# PCB_LCEDA.net
KiCad netlist of a schematic drawn in EasyEDA
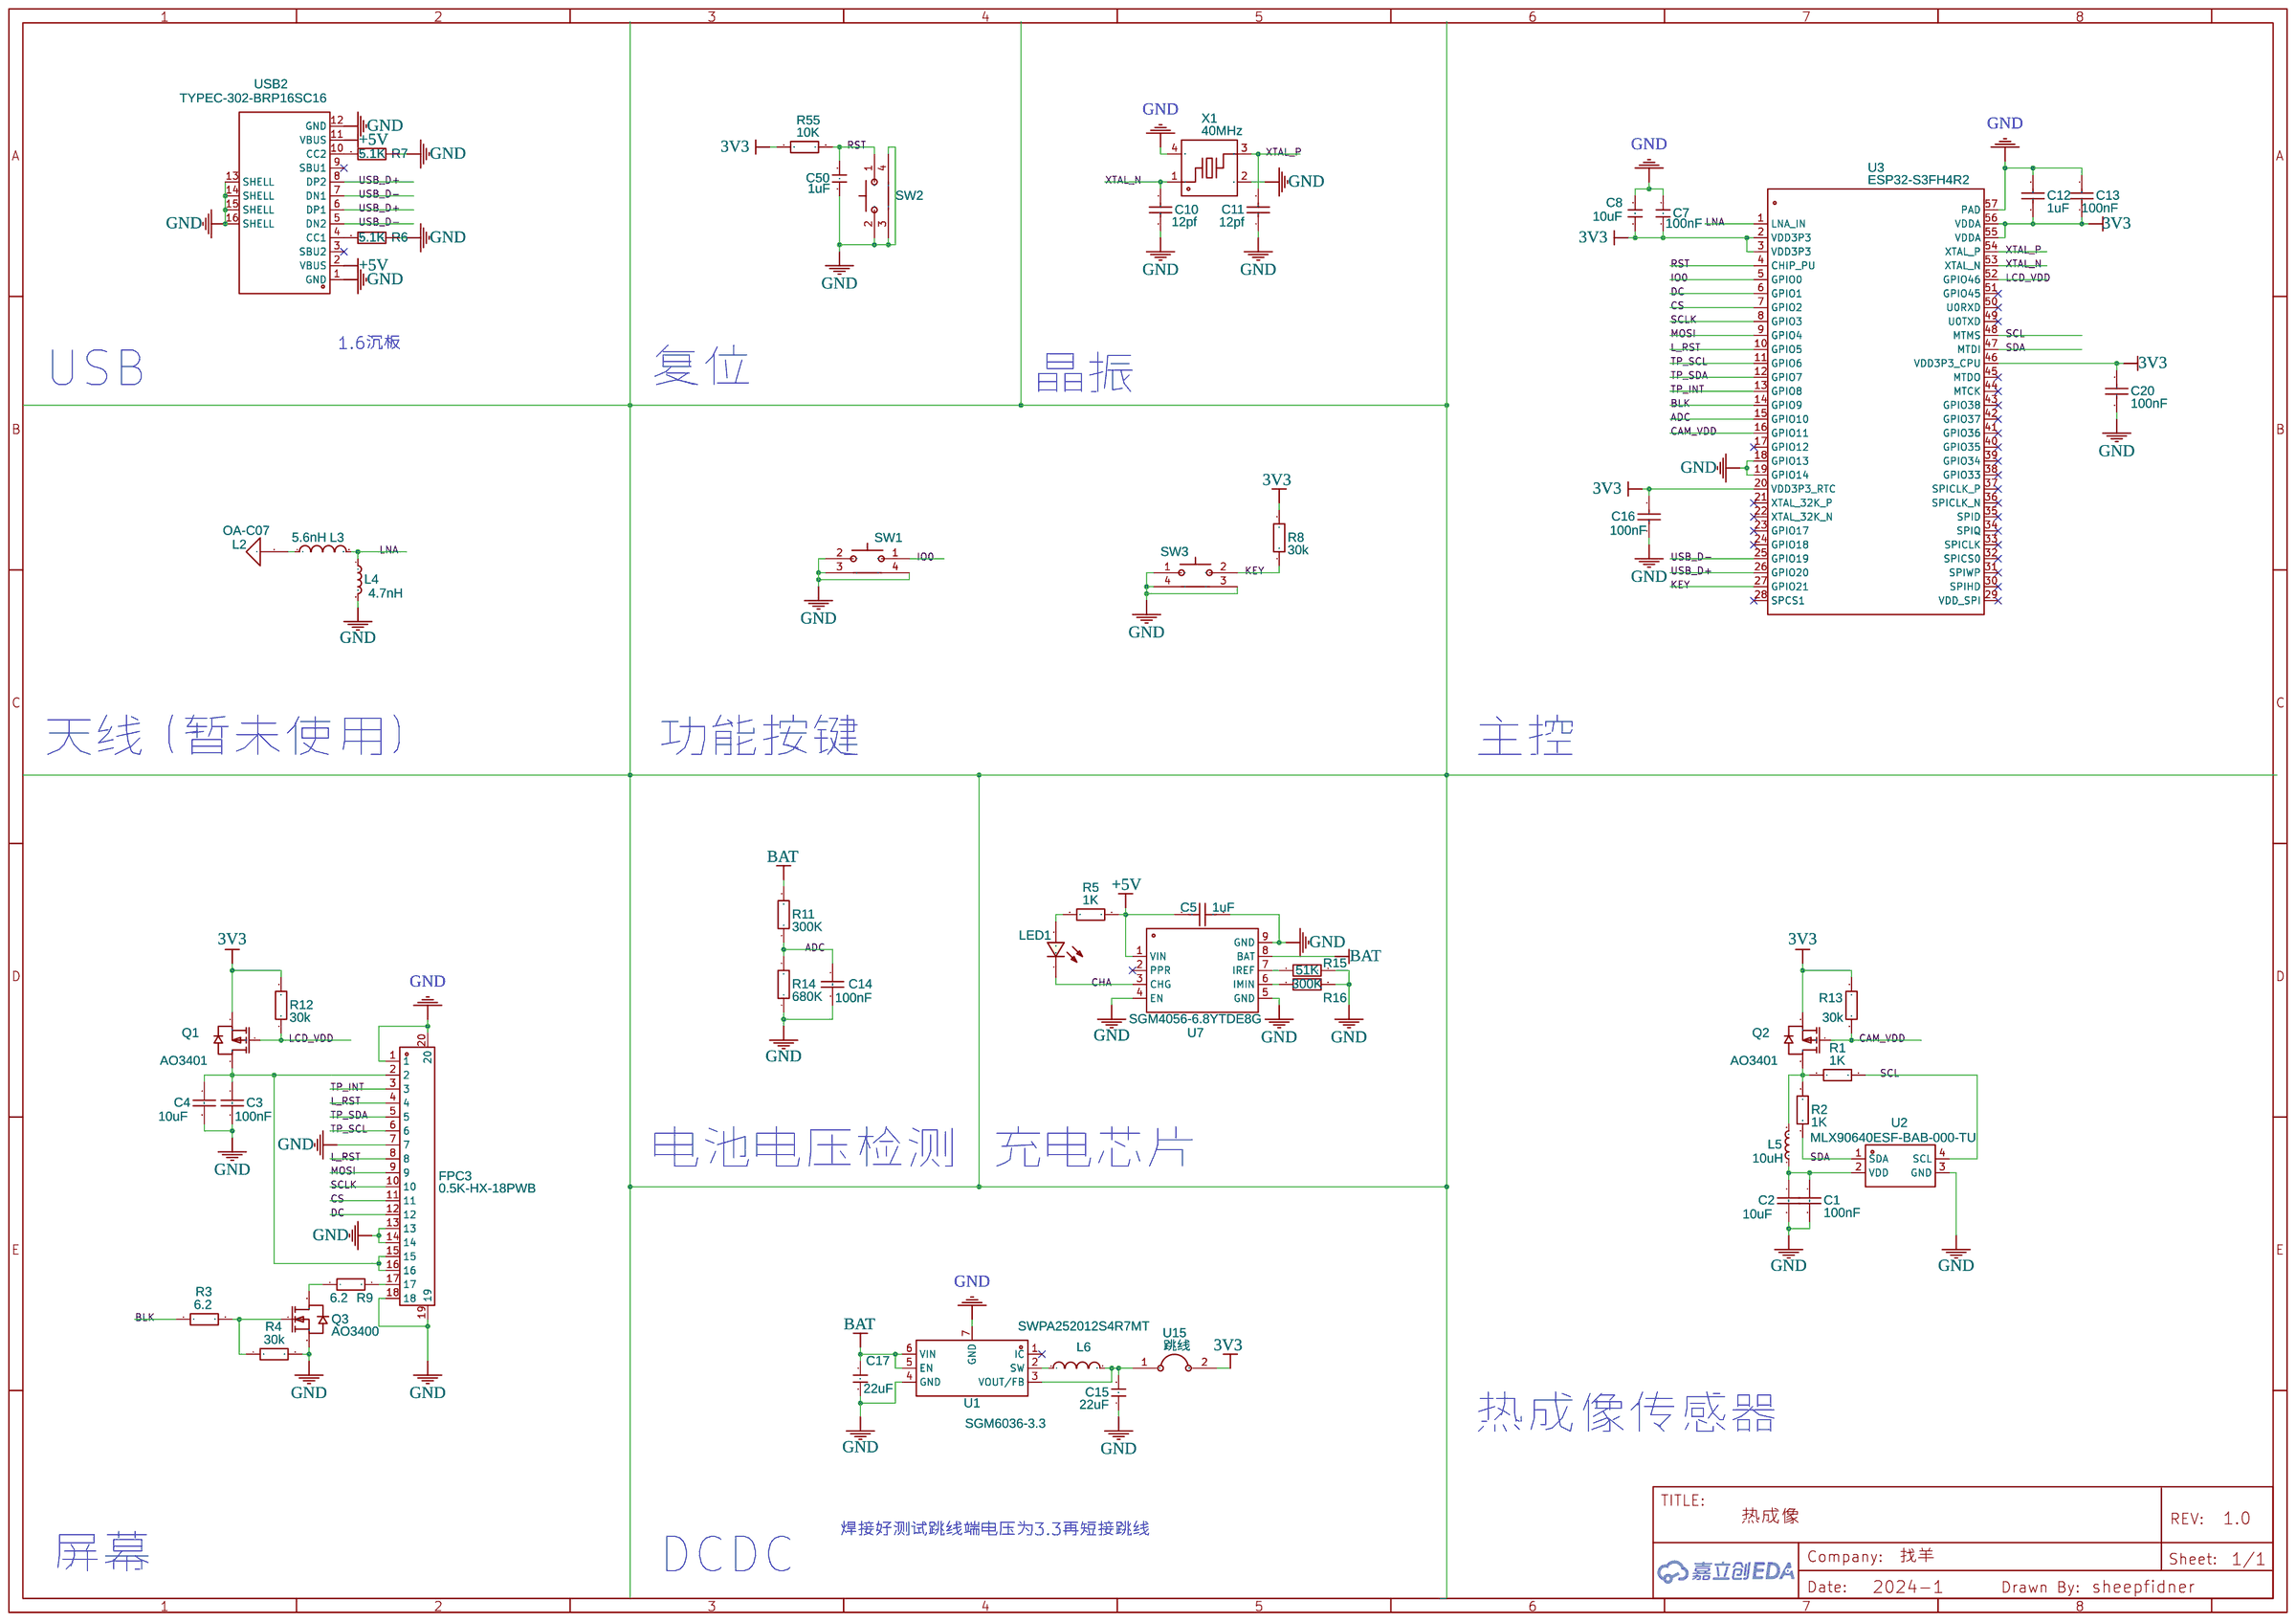
[diagram p0: schematic sheet]

(export (version "E")
  (design (tool "Eeschema 10.0.6"))
  (components
    (comp (ref "C1") (value "100nF") (libsource (lib "") (part "cap 0603_3")))
    (comp (ref "C2") (value "10uF") (libsource (lib "") (part "cap 0603")))
    (comp (ref "C3") (value "100nF") (libsource (lib "") (part "cap 0603")))
    (comp (ref "C4") (value "10uF") (libsource (lib "") (part "cap 0603")))
    (comp (ref "C5") (value "1uF") (libsource (lib "") (part "cap 0603_4")))
    (comp (ref "C7") (value "100nF") (libsource (lib "") (part "cap 0603_1")))
    (comp (ref "C8") (value "10uF") (libsource (lib "") (part "cap 0603_2")))
    (comp (ref "C10") (value "12pf") (libsource (lib "") (part "cap 0402")))
    (comp (ref "C11") (value "12pf") (libsource (lib "") (part "cap 0402_1")))
    (comp (ref "C12") (value "1uF") (libsource (lib "") (part "cap 0402_2")))
    (comp (ref "C13") (value "100nF") (libsource (lib "") (part "cap 0402_2")))
    (comp (ref "C14") (value "100nF") (libsource (lib "") (part "cap 0603")))
    (comp (ref "C15") (value "22uF") (libsource (lib "") (part "cap 0603_2")))
    (comp (ref "C16") (value "100nF") (libsource (lib "") (part "cap 0402")))
    (comp (ref "C17") (value "22uF") (libsource (lib "") (part "cap 0603_1")))
    (comp (ref "C20") (value "100nF") (libsource (lib "") (part "cap 0402")))
    (comp (ref "C50") (value "1uF") (libsource (lib "") (part "cap 0603_1")))
    (comp (ref "FPC3") (value "0.5K-HX-18PWB") (libsource (lib "") (part "0.5K-HX-18PWB")))
    (comp (ref "L2") (value "OA-C07") (libsource (lib "") (part "OA-C07")))
    (comp (ref "L3") (value "5.6nH") (libsource (lib "") (part "L-0402")))
    (comp (ref "L4") (value "4.7nH") (libsource (lib "") (part "L 0603")))
    (comp (ref "L5") (value "10uH") (libsource (lib "") (part "0805-L")))
    (comp (ref "L6") (value "SWPA252012S4R7MT") (libsource (lib "") (part "SWPA252012S2R2N")))
    (comp (ref "LED1") (value "led-0603") (libsource (lib "") (part "led-0603")))
    (comp (ref "Q1")
      (value "AO3401")
      (fields (field (name "Manufacturer") "IDCHIP(英锐芯)"))
      (libsource (lib "") (part "AO3401_C2848197"))
    )
    (comp (ref "Q2")
      (value "AO3401")
      (fields (field (name "Manufacturer") "IDCHIP(英锐芯)"))
      (libsource (lib "") (part "AO3401_C2848197"))
    )
    (comp (ref "Q3")
      (value "AO3400")
      (fields (field (name "Manufacturer") "IDCHIP(英锐芯)"))
      (libsource (lib "") (part "AO3400_C2848198"))
    )
    (comp (ref "R1") (value "1K") (libsource (lib "") (part "res-0603_1")))
    (comp (ref "R2") (value "1K") (libsource (lib "") (part "res-0603_2")))
    (comp (ref "R3") (value "6.2") (libsource (lib "") (part "res-0603")))
    (comp (ref "R4") (value "30k") (libsource (lib "") (part "res-0603")))
    (comp (ref "R5") (value "1K") (libsource (lib "") (part "res-0603_1")))
    (comp (ref "R6") (value "5.1K") (libsource (lib "") (part "res-0603")))
    (comp (ref "R7") (value "5.1K") (libsource (lib "") (part "res-0603_1")))
    (comp (ref "R8") (value "30k") (libsource (lib "") (part "res-0603_2")))
    (comp (ref "R9") (value "6.2") (libsource (lib "") (part "res-0603")))
    (comp (ref "R11") (value "300K") (libsource (lib "") (part "res-0603_2")))
    (comp (ref "R12") (value "30k") (libsource (lib "") (part "res-0603_2")))
    (comp (ref "R13") (value "30k") (libsource (lib "") (part "res-0603_2")))
    (comp (ref "R14") (value "680K") (libsource (lib "") (part "res-0603_2")))
    (comp (ref "R15") (value "51K") (libsource (lib "") (part "res-0603_1")))
    (comp (ref "R16") (value "300K") (libsource (lib "") (part "res-0603_1")))
    (comp (ref "R55") (value "10K") (libsource (lib "") (part "res-0603")))
    (comp (ref "SW1") (value "1TS003B") (libsource (lib "") (part "1TS003B-1900-3500A")))
    (comp (ref "SW2") (value "1TS003B") (libsource (lib "") (part "1TS003B-1900-3500A_2")))
    (comp (ref "SW3") (value "1TS003B") (libsource (lib "") (part "1TS003B-1900-3500A_1")))
    (comp (ref "U1") (value "SGM6036-3.3") (libsource (lib "") (part "SGM6036-ADJYUDT6G/TR")))
    (comp (ref "U2") (value "MLX90640ESF-BAB-000-TU") (libsource (lib "") (part "MLX90640ESF-BAB-000-TU")))
    (comp (ref "U3") (value "ESP32-S3FH4R2") (libsource (lib "") (part "ESP32-S3R2")))
    (comp (ref "U7") (value "SGM4056-6.8YTDE8G") (libsource (lib "") (part "SGM4056-6.8YTDE8G")))
    (comp (ref "U15") (value "跳线") (libsource (lib "") (part "跳线")))
    (comp (ref "USB2")
      (value "TYPEC-302-BRP16SC16")
      (fields (field (name "Manufacturer") "XUNPU(讯普)"))
      (libsource (lib "") (part "TYPEC-302-BRP16SC16"))
    )
    (comp (ref "X1") (value "40MHz") (libsource (lib "") (part "2016_4P")))
  )
  (nets
    (net (code "1") (name "+5V") (class "Default")
      (node (ref "C5") (pin "1") (pinfunction "1_1") (pintype "unspecified"))
      (node (ref "R5") (pin "1") (pinfunction "1_1") (pintype "unspecified"))
      (node (ref "U7") (pin "1") (pinfunction "VIN_1") (pintype "unspecified"))
      (node (ref "USB2") (pin "11") (pinfunction "VBUS_11") (pintype "unspecified"))
      (node (ref "USB2") (pin "2") (pinfunction "VBUS_2") (pintype "unspecified"))
    )
    (net (code "2") (name "/ADC") (class "Default")
      (node (ref "C14") (pin "1") (pinfunction "1_1") (pintype "unspecified"))
      (node (ref "R11") (pin "1") (pinfunction "1_1") (pintype "unspecified"))
      (node (ref "R14") (pin "2") (pinfunction "2_2") (pintype "unspecified"))
      (node (ref "U3") (pin "15") (pinfunction "GPIO10_15") (pintype "unspecified"))
    )
    (net (code "3") (name "/BLK") (class "Default")
      (node (ref "R3") (pin "1") (pinfunction "1_1") (pintype "unspecified"))
      (node (ref "U3") (pin "14") (pinfunction "GPIO9_14") (pintype "unspecified"))
    )
    (net (code "4") (name "/CAM_VDD") (class "Default")
      (node (ref "Q2") (pin "1") (pinfunction "G_1") (pintype "unspecified"))
      (node (ref "R13") (pin "1") (pinfunction "1_1") (pintype "unspecified"))
      (node (ref "U3") (pin "16") (pinfunction "GPIO11_16") (pintype "unspecified"))
    )
    (net (code "5") (name "/CHA") (class "Default")
      (node (ref "LED1") (pin "1") (pinfunction "C_1") (pintype "input"))
      (node (ref "U7") (pin "3") (pinfunction "CHG_3") (pintype "unspecified"))
    )
    (net (code "6") (name "/CS") (class "Default")
      (node (ref "FPC3") (pin "11") (pinfunction "11_11") (pintype "unspecified"))
      (node (ref "U3") (pin "7") (pinfunction "GPIO2_7") (pintype "unspecified"))
    )
    (net (code "7") (name "/DC") (class "Default")
      (node (ref "FPC3") (pin "12") (pinfunction "12_12") (pintype "unspecified"))
      (node (ref "U3") (pin "6") (pinfunction "GPIO1_6") (pintype "unspecified"))
    )
    (net (code "8") (name "/IO0") (class "Default")
      (node (ref "SW1") (pin "1") (pinfunction "1_1") (pintype "unspecified"))
      (node (ref "U3") (pin "5") (pinfunction "GPIO0_5") (pintype "unspecified"))
    )
    (net (code "9") (name "/KEY") (class "Default")
      (node (ref "R8") (pin "1") (pinfunction "1_1") (pintype "unspecified"))
      (node (ref "SW3") (pin "2") (pinfunction "2_2") (pintype "unspecified"))
      (node (ref "U3") (pin "27") (pinfunction "GPIO21_27") (pintype "unspecified"))
    )
    (net (code "10") (name "/LCD_VDD") (class "Default")
      (node (ref "Q1") (pin "1") (pinfunction "G_1") (pintype "unspecified"))
      (node (ref "R12") (pin "1") (pinfunction "1_1") (pintype "unspecified"))
      (node (ref "U3") (pin "52") (pinfunction "GPIO46_52") (pintype "unspecified"))
    )
    (net (code "11") (name "/LNA") (class "Default")
      (node (ref "L3") (pin "2") (pinfunction "2_2") (pintype "unspecified"))
      (node (ref "L4") (pin "1") (pinfunction "1_1") (pintype "unspecified"))
      (node (ref "U3") (pin "1") (pinfunction "LNA_IN_1") (pintype "unspecified"))
    )
    (net (code "12") (name "/L_RST") (class "Default")
      (node (ref "FPC3") (pin "4") (pinfunction "4_4") (pintype "unspecified"))
      (node (ref "FPC3") (pin "8") (pinfunction "8_8") (pintype "unspecified"))
      (node (ref "U3") (pin "10") (pinfunction "GPIO5_10") (pintype "unspecified"))
    )
    (net (code "13") (name "/MOSI") (class "Default")
      (node (ref "FPC3") (pin "9") (pinfunction "9_9") (pintype "unspecified"))
      (node (ref "U3") (pin "9") (pinfunction "GPIO4_9") (pintype "unspecified"))
    )
    (net (code "14") (name "/RST") (class "Default")
      (node (ref "C50") (pin "2") (pinfunction "2_2") (pintype "unspecified"))
      (node (ref "R55") (pin "2") (pinfunction "2_2") (pintype "unspecified"))
      (node (ref "SW2") (pin "1") (pinfunction "1_1") (pintype "unspecified"))
      (node (ref "U3") (pin "4") (pinfunction "CHIP_PU_4") (pintype "unspecified"))
    )
    (net (code "15") (name "/SCL") (class "Default")
      (node (ref "R1") (pin "1") (pinfunction "1_1") (pintype "unspecified"))
      (node (ref "U2") (pin "4") (pinfunction "SCL_4") (pintype "unspecified"))
      (node (ref "U3") (pin "48") (pinfunction "MTMS_48") (pintype "unspecified"))
    )
    (net (code "16") (name "/SCLK") (class "Default")
      (node (ref "FPC3") (pin "10") (pinfunction "10_10") (pintype "unspecified"))
      (node (ref "U3") (pin "8") (pinfunction "GPIO3_8") (pintype "unspecified"))
    )
    (net (code "17") (name "/SDA") (class "Default")
      (node (ref "R2") (pin "1") (pinfunction "1_1") (pintype "unspecified"))
      (node (ref "U2") (pin "1") (pinfunction "SDA_1") (pintype "unspecified"))
      (node (ref "U3") (pin "47") (pinfunction "MTDI_47") (pintype "unspecified"))
    )
    (net (code "18") (name "/TP_INT") (class "Default")
      (node (ref "FPC3") (pin "3") (pinfunction "3_3") (pintype "unspecified"))
      (node (ref "U3") (pin "13") (pinfunction "GPIO8_13") (pintype "unspecified"))
    )
    (net (code "19") (name "/TP_SCL") (class "Default")
      (node (ref "FPC3") (pin "6") (pinfunction "6_6") (pintype "unspecified"))
      (node (ref "U3") (pin "11") (pinfunction "GPIO6_11") (pintype "unspecified"))
    )
    (net (code "20") (name "/TP_SDA") (class "Default")
      (node (ref "FPC3") (pin "5") (pinfunction "5_5") (pintype "unspecified"))
      (node (ref "U3") (pin "12") (pinfunction "GPIO7_12") (pintype "unspecified"))
    )
    (net (code "21") (name "/USB_D+") (class "Default")
      (node (ref "U3") (pin "26") (pinfunction "GPIO20_26") (pintype "unspecified"))
      (node (ref "USB2") (pin "6") (pinfunction "DP1_6") (pintype "unspecified"))
      (node (ref "USB2") (pin "8") (pinfunction "DP2_8") (pintype "unspecified"))
    )
    (net (code "22") (name "/USB_D-") (class "Default")
      (node (ref "U3") (pin "25") (pinfunction "GPIO19_25") (pintype "unspecified"))
      (node (ref "USB2") (pin "5") (pinfunction "DN2_5") (pintype "unspecified"))
      (node (ref "USB2") (pin "7") (pinfunction "DN1_7") (pintype "unspecified"))
    )
    (net (code "23") (name "/XTAL_N") (class "Default")
      (node (ref "C10") (pin "1") (pinfunction "1_1") (pintype "input"))
      (node (ref "U3") (pin "53") (pinfunction "XTAL_N_53") (pintype "unspecified"))
      (node (ref "X1") (pin "1") (pinfunction "1_1") (pintype "input"))
    )
    (net (code "24") (name "/XTAL_P") (class "Default")
      (node (ref "C11") (pin "2") (pinfunction "2_2") (pintype "input"))
      (node (ref "U3") (pin "54") (pinfunction "XTAL_P_54") (pintype "unspecified"))
      (node (ref "X1") (pin "3") (pinfunction "3_3") (pintype "input"))
    )
    (net (code "25") (name "3V3") (class "Default")
      (node (ref "C12") (pin "2") (pinfunction "2_2") (pintype "input"))
      (node (ref "C13") (pin "2") (pinfunction "2_2") (pintype "input"))
      (node (ref "C16") (pin "1") (pinfunction "1_1") (pintype "input"))
      (node (ref "C20") (pin "1") (pinfunction "1_1") (pintype "input"))
      (node (ref "C7") (pin "1") (pinfunction "1_1") (pintype "unspecified"))
      (node (ref "C8") (pin "1") (pinfunction "1_1") (pintype "unspecified"))
      (node (ref "Q1") (pin "2") (pinfunction "S_2") (pintype "unspecified"))
      (node (ref "Q2") (pin "2") (pinfunction "S_2") (pintype "unspecified"))
      (node (ref "R12") (pin "2") (pinfunction "2_2") (pintype "unspecified"))
      (node (ref "R13") (pin "2") (pinfunction "2_2") (pintype "unspecified"))
      (node (ref "R55") (pin "1") (pinfunction "1_1") (pintype "unspecified"))
      (node (ref "R8") (pin "2") (pinfunction "2_2") (pintype "unspecified"))
      (node (ref "U15") (pin "2") (pinfunction "2_2") (pintype "unspecified"))
      (node (ref "U3") (pin "2") (pinfunction "VDD3P3_2") (pintype "unspecified"))
      (node (ref "U3") (pin "20") (pinfunction "VDD3P3_RTC_20") (pintype "unspecified"))
      (node (ref "U3") (pin "3") (pinfunction "VDD3P3_3") (pintype "unspecified"))
      (node (ref "U3") (pin "46") (pinfunction "VDD3P3_CPU_46") (pintype "unspecified"))
      (node (ref "U3") (pin "55") (pinfunction "VDDA_55") (pintype "unspecified"))
      (node (ref "U3") (pin "56") (pinfunction "VDDA_56") (pintype "unspecified"))
    )
    (net (code "26") (name "BAT") (class "Default")
      (node (ref "C17") (pin "2") (pinfunction "2_2") (pintype "unspecified"))
      (node (ref "R11") (pin "2") (pinfunction "2_2") (pintype "unspecified"))
      (node (ref "U1") (pin "5") (pinfunction "EN_5") (pintype "unspecified"))
      (node (ref "U1") (pin "6") (pinfunction "VIN_6") (pintype "unspecified"))
      (node (ref "U7") (pin "8") (pinfunction "BAT_8") (pintype "unspecified"))
    )
    (net (code "27") (name "GND") (class "Default")
      (node (ref "C1") (pin "2") (pinfunction "2_2") (pintype "unspecified"))
      (node (ref "C10") (pin "2") (pinfunction "2_2") (pintype "input"))
      (node (ref "C11") (pin "1") (pinfunction "1_1") (pintype "input"))
      (node (ref "C12") (pin "1") (pinfunction "1_1") (pintype "input"))
      (node (ref "C13") (pin "1") (pinfunction "1_1") (pintype "input"))
      (node (ref "C14") (pin "2") (pinfunction "2_2") (pintype "unspecified"))
      (node (ref "C15") (pin "1") (pinfunction "1_1") (pintype "unspecified"))
      (node (ref "C16") (pin "2") (pinfunction "2_2") (pintype "input"))
      (node (ref "C17") (pin "1") (pinfunction "1_1") (pintype "unspecified"))
      (node (ref "C2") (pin "2") (pinfunction "2_2") (pintype "unspecified"))
      (node (ref "C20") (pin "2") (pinfunction "2_2") (pintype "input"))
      (node (ref "C3") (pin "2") (pinfunction "2_2") (pintype "unspecified"))
      (node (ref "C4") (pin "2") (pinfunction "2_2") (pintype "unspecified"))
      (node (ref "C5") (pin "2") (pinfunction "2_2") (pintype "unspecified"))
      (node (ref "C50") (pin "1") (pinfunction "1_1") (pintype "unspecified"))
      (node (ref "C7") (pin "2") (pinfunction "2_2") (pintype "unspecified"))
      (node (ref "C8") (pin "2") (pinfunction "2_2") (pintype "unspecified"))
      (node (ref "FPC3") (pin "1") (pinfunction "1_1") (pintype "unspecified"))
      (node (ref "FPC3") (pin "13") (pinfunction "13_13") (pintype "unspecified"))
      (node (ref "FPC3") (pin "14") (pinfunction "14_14") (pintype "unspecified"))
      (node (ref "FPC3") (pin "18") (pinfunction "18_18") (pintype "unspecified"))
      (node (ref "FPC3") (pin "19") (pinfunction "19_19") (pintype "unspecified"))
      (node (ref "FPC3") (pin "20") (pinfunction "20_20") (pintype "unspecified"))
      (node (ref "FPC3") (pin "7") (pinfunction "7_7") (pintype "unspecified"))
      (node (ref "L4") (pin "2") (pinfunction "2_2") (pintype "unspecified"))
      (node (ref "Q3") (pin "2") (pinfunction "S_2") (pintype "unspecified"))
      (node (ref "R14") (pin "1") (pinfunction "1_1") (pintype "unspecified"))
      (node (ref "R15") (pin "1") (pinfunction "1_1") (pintype "unspecified"))
      (node (ref "R16") (pin "1") (pinfunction "1_1") (pintype "unspecified"))
      (node (ref "R4") (pin "2") (pinfunction "2_2") (pintype "unspecified"))
      (node (ref "R6") (pin "2") (pinfunction "2_2") (pintype "unspecified"))
      (node (ref "R7") (pin "1") (pinfunction "1_1") (pintype "unspecified"))
      (node (ref "SW1") (pin "2") (pinfunction "2_2") (pintype "unspecified"))
      (node (ref "SW1") (pin "3") (pinfunction "3_3") (pintype "unspecified"))
      (node (ref "SW1") (pin "4") (pinfunction "4_4") (pintype "unspecified"))
      (node (ref "SW2") (pin "2") (pinfunction "2_2") (pintype "unspecified"))
      (node (ref "SW2") (pin "3") (pinfunction "3_3") (pintype "unspecified"))
      (node (ref "SW2") (pin "4") (pinfunction "4_4") (pintype "unspecified"))
      (node (ref "SW3") (pin "1") (pinfunction "1_1") (pintype "unspecified"))
      (node (ref "SW3") (pin "3") (pinfunction "3_3") (pintype "unspecified"))
      (node (ref "SW3") (pin "4") (pinfunction "4_4") (pintype "unspecified"))
      (node (ref "U1") (pin "4") (pinfunction "GND_4") (pintype "unspecified"))
      (node (ref "U1") (pin "7") (pinfunction "GND_7") (pintype "unspecified"))
      (node (ref "U2") (pin "3") (pinfunction "GND_3") (pintype "unspecified"))
      (node (ref "U3") (pin "18") (pinfunction "GPIO13_18") (pintype "unspecified"))
      (node (ref "U3") (pin "19") (pinfunction "GPIO14_19") (pintype "unspecified"))
      (node (ref "U3") (pin "57") (pinfunction "PAD_57") (pintype "unspecified"))
      (node (ref "U7") (pin "4") (pinfunction "EN_4") (pintype "unspecified"))
      (node (ref "U7") (pin "5") (pinfunction "GND_5") (pintype "unspecified"))
      (node (ref "U7") (pin "9") (pinfunction "GND_9") (pintype "unspecified"))
      (node (ref "USB2") (pin "1") (pinfunction "GND_1") (pintype "unspecified"))
      (node (ref "USB2") (pin "12") (pinfunction "GND_12") (pintype "unspecified"))
      (node (ref "USB2") (pin "13") (pinfunction "SHELL_13") (pintype "unspecified"))
      (node (ref "USB2") (pin "14") (pinfunction "SHELL_14") (pintype "unspecified"))
      (node (ref "USB2") (pin "15") (pinfunction "SHELL_15") (pintype "unspecified"))
      (node (ref "USB2") (pin "16") (pinfunction "SHELL_16") (pintype "unspecified"))
      (node (ref "X1") (pin "2") (pinfunction "GND_2") (pintype "input"))
      (node (ref "X1") (pin "4") (pinfunction "GND_4") (pintype "input"))
    )
    (net (code "28") (name "Net-(FPC3-Pad17)") (class "Default")
      (node (ref "FPC3") (pin "17") (pinfunction "17_17") (pintype "unspecified"))
      (node (ref "R9") (pin "2") (pinfunction "2_2") (pintype "unspecified"))
    )
    (net (code "29") (name "Net-(L2-Pad1)") (class "Default")
      (node (ref "L2") (pin "1") (pinfunction "1_1") (pintype "unspecified"))
      (node (ref "L3") (pin "1") (pinfunction "1_1") (pintype "unspecified"))
    )
    (net (code "30") (name "Net-(LED1-A)") (class "Default")
      (node (ref "LED1") (pin "2") (pinfunction "A_2") (pintype "input"))
      (node (ref "R5") (pin "2") (pinfunction "2_2") (pintype "unspecified"))
    )
    (net (code "31") (name "Net-(Q1-D)") (class "Default")
      (node (ref "C3") (pin "1") (pinfunction "1_1") (pintype "unspecified"))
      (node (ref "C4") (pin "1") (pinfunction "1_1") (pintype "unspecified"))
      (node (ref "FPC3") (pin "15") (pinfunction "15_15") (pintype "unspecified"))
      (node (ref "FPC3") (pin "16") (pinfunction "16_16") (pintype "unspecified"))
      (node (ref "FPC3") (pin "2") (pinfunction "2_2") (pintype "unspecified"))
      (node (ref "Q1") (pin "3") (pinfunction "D_3") (pintype "unspecified"))
    )
    (net (code "32") (name "Net-(Q2-D)") (class "Default")
      (node (ref "L5") (pin "2") (pinfunction "2_2") (pintype "unspecified"))
      (node (ref "Q2") (pin "3") (pinfunction "D_3") (pintype "unspecified"))
      (node (ref "R1") (pin "2") (pinfunction "2_2") (pintype "unspecified"))
      (node (ref "R2") (pin "2") (pinfunction "2_2") (pintype "unspecified"))
    )
    (net (code "33") (name "Net-(Q3-D)") (class "Default")
      (node (ref "Q3") (pin "3") (pinfunction "D_3") (pintype "unspecified"))
      (node (ref "R9") (pin "1") (pinfunction "1_1") (pintype "unspecified"))
    )
    (net (code "34") (name "Net-(Q3-G)") (class "Default")
      (node (ref "Q3") (pin "1") (pinfunction "G_1") (pintype "unspecified"))
      (node (ref "R3") (pin "2") (pinfunction "2_2") (pintype "unspecified"))
      (node (ref "R4") (pin "1") (pinfunction "1_1") (pintype "unspecified"))
    )
    (net (code "35") (name "Net-(U1-SW)") (class "Default")
      (node (ref "L6") (pin "1") (pinfunction "1_1") (pintype "unspecified"))
      (node (ref "U1") (pin "2") (pinfunction "SW_2") (pintype "unspecified"))
    )
    (net (code "36") (name "Net-(U1-VOUT{slash}FB)") (class "Default")
      (node (ref "C15") (pin "2") (pinfunction "2_2") (pintype "unspecified"))
      (node (ref "L6") (pin "2") (pinfunction "2_2") (pintype "unspecified"))
      (node (ref "U1") (pin "3") (pinfunction "VOUT/FB_3") (pintype "unspecified"))
      (node (ref "U15") (pin "1") (pinfunction "1_1") (pintype "unspecified"))
    )
    (net (code "37") (name "Net-(U2-VDD)") (class "Default")
      (node (ref "C1") (pin "1") (pinfunction "1_1") (pintype "unspecified"))
      (node (ref "C2") (pin "1") (pinfunction "1_1") (pintype "unspecified"))
      (node (ref "L5") (pin "1") (pinfunction "1_1") (pintype "unspecified"))
      (node (ref "U2") (pin "2") (pinfunction "VDD_2") (pintype "unspecified"))
    )
    (net (code "38") (name "Net-(U7-IMIN)") (class "Default")
      (node (ref "R16") (pin "2") (pinfunction "2_2") (pintype "unspecified"))
      (node (ref "U7") (pin "6") (pinfunction "IMIN_6") (pintype "unspecified"))
    )
    (net (code "39") (name "Net-(U7-IREF)") (class "Default")
      (node (ref "R15") (pin "2") (pinfunction "2_2") (pintype "unspecified"))
      (node (ref "U7") (pin "7") (pinfunction "IREF_7") (pintype "unspecified"))
    )
    (net (code "40") (name "Net-(USB2-CC1)") (class "Default")
      (node (ref "R6") (pin "1") (pinfunction "1_1") (pintype "unspecified"))
      (node (ref "USB2") (pin "4") (pinfunction "CC1_4") (pintype "unspecified"))
    )
    (net (code "41") (name "Net-(USB2-CC2)") (class "Default")
      (node (ref "R7") (pin "2") (pinfunction "2_2") (pintype "unspecified"))
      (node (ref "USB2") (pin "10") (pinfunction "CC2_10") (pintype "unspecified"))
    )
    (net (code "42") (name "unconnected-(U1-IC-Pad1)") (class "Default")
      (node (ref "U1") (pin "1") (pinfunction "IC_1") (pintype "unspecified+no_connect"))
    )
    (net (code "43") (name "unconnected-(U3-GPIO12-Pad17)") (class "Default")
      (node (ref "U3") (pin "17") (pinfunction "GPIO12_17") (pintype "unspecified+no_connect"))
    )
    (net (code "44") (name "unconnected-(U3-GPIO17-Pad23)") (class "Default")
      (node (ref "U3") (pin "23") (pinfunction "GPIO17_23") (pintype "unspecified+no_connect"))
    )
    (net (code "45") (name "unconnected-(U3-GPIO18-Pad24)") (class "Default")
      (node (ref "U3") (pin "24") (pinfunction "GPIO18_24") (pintype "unspecified+no_connect"))
    )
    (net (code "46") (name "unconnected-(U3-GPIO33-Pad38)") (class "Default")
      (node (ref "U3") (pin "38") (pinfunction "GPIO33_38") (pintype "unspecified+no_connect"))
    )
    (net (code "47") (name "unconnected-(U3-GPIO34-Pad39)") (class "Default")
      (node (ref "U3") (pin "39") (pinfunction "GPIO34_39") (pintype "unspecified+no_connect"))
    )
    (net (code "48") (name "unconnected-(U3-GPIO35-Pad40)") (class "Default")
      (node (ref "U3") (pin "40") (pinfunction "GPIO35_40") (pintype "unspecified+no_connect"))
    )
    (net (code "49") (name "unconnected-(U3-GPIO36-Pad41)") (class "Default")
      (node (ref "U3") (pin "41") (pinfunction "GPIO36_41") (pintype "unspecified+no_connect"))
    )
    (net (code "50") (name "unconnected-(U3-GPIO37-Pad42)") (class "Default")
      (node (ref "U3") (pin "42") (pinfunction "GPIO37_42") (pintype "unspecified+no_connect"))
    )
    (net (code "51") (name "unconnected-(U3-GPIO38-Pad43)") (class "Default")
      (node (ref "U3") (pin "43") (pinfunction "GPIO38_43") (pintype "unspecified+no_connect"))
    )
    (net (code "52") (name "unconnected-(U3-GPIO45-Pad51)") (class "Default")
      (node (ref "U3") (pin "51") (pinfunction "GPIO45_51") (pintype "unspecified+no_connect"))
    )
    (net (code "53") (name "unconnected-(U3-MTCK-Pad44)") (class "Default")
      (node (ref "U3") (pin "44") (pinfunction "MTCK_44") (pintype "unspecified+no_connect"))
    )
    (net (code "54") (name "unconnected-(U3-MTDO-Pad45)") (class "Default")
      (node (ref "U3") (pin "45") (pinfunction "MTDO_45") (pintype "unspecified+no_connect"))
    )
    (net (code "55") (name "unconnected-(U3-SPCS1-Pad28)") (class "Default")
      (node (ref "U3") (pin "28") (pinfunction "SPCS1_28") (pintype "unspecified+no_connect"))
    )
    (net (code "56") (name "unconnected-(U3-SPICLK-Pad33)") (class "Default")
      (node (ref "U3") (pin "33") (pinfunction "SPICLK_33") (pintype "unspecified+no_connect"))
    )
    (net (code "57") (name "unconnected-(U3-SPICLK_N-Pad36)") (class "Default")
      (node (ref "U3") (pin "36") (pinfunction "SPICLK_N_36") (pintype "unspecified+no_connect"))
    )
    (net (code "58") (name "unconnected-(U3-SPICLK_P-Pad37)") (class "Default")
      (node (ref "U3") (pin "37") (pinfunction "SPICLK_P_37") (pintype "unspecified+no_connect"))
    )
    (net (code "59") (name "unconnected-(U3-SPICS0-Pad32)") (class "Default")
      (node (ref "U3") (pin "32") (pinfunction "SPICS0_32") (pintype "unspecified+no_connect"))
    )
    (net (code "60") (name "unconnected-(U3-SPID-Pad35)") (class "Default")
      (node (ref "U3") (pin "35") (pinfunction "SPID_35") (pintype "unspecified+no_connect"))
    )
    (net (code "61") (name "unconnected-(U3-SPIHD-Pad30)") (class "Default")
      (node (ref "U3") (pin "30") (pinfunction "SPIHD_30") (pintype "unspecified+no_connect"))
    )
    (net (code "62") (name "unconnected-(U3-SPIQ-Pad34)") (class "Default")
      (node (ref "U3") (pin "34") (pinfunction "SPIQ_34") (pintype "unspecified+no_connect"))
    )
    (net (code "63") (name "unconnected-(U3-SPIWP-Pad31)") (class "Default")
      (node (ref "U3") (pin "31") (pinfunction "SPIWP_31") (pintype "unspecified+no_connect"))
    )
    (net (code "64") (name "unconnected-(U3-U0RXD-Pad50)") (class "Default")
      (node (ref "U3") (pin "50") (pinfunction "U0RXD_50") (pintype "unspecified+no_connect"))
    )
    (net (code "65") (name "unconnected-(U3-U0TXD-Pad49)") (class "Default")
      (node (ref "U3") (pin "49") (pinfunction "U0TXD_49") (pintype "unspecified+no_connect"))
    )
    (net (code "66") (name "unconnected-(U3-VDD_SPI-Pad29)") (class "Default")
      (node (ref "U3") (pin "29") (pinfunction "VDD_SPI_29") (pintype "unspecified+no_connect"))
    )
    (net (code "67") (name "unconnected-(U3-XTAL_32K_N-Pad22)") (class "Default")
      (node (ref "U3") (pin "22") (pinfunction "XTAL_32K_N_22") (pintype "unspecified+no_connect"))
    )
    (net (code "68") (name "unconnected-(U3-XTAL_32K_P-Pad21)") (class "Default")
      (node (ref "U3") (pin "21") (pinfunction "XTAL_32K_P_21") (pintype "unspecified+no_connect"))
    )
    (net (code "69") (name "unconnected-(U7-PPR-Pad2)") (class "Default")
      (node (ref "U7") (pin "2") (pinfunction "PPR_2") (pintype "unspecified"))
    )
    (net (code "70") (name "unconnected-(USB2-SBU1-Pad9)") (class "Default")
      (node (ref "USB2") (pin "9") (pinfunction "SBU1_9") (pintype "unspecified+no_connect"))
    )
    (net (code "71") (name "unconnected-(USB2-SBU2-Pad3)") (class "Default")
      (node (ref "USB2") (pin "3") (pinfunction "SBU2_3") (pintype "unspecified+no_connect"))
    )
  )
)
